# W076X.net
KiCad netlist of a schematic drawn in EAGLE
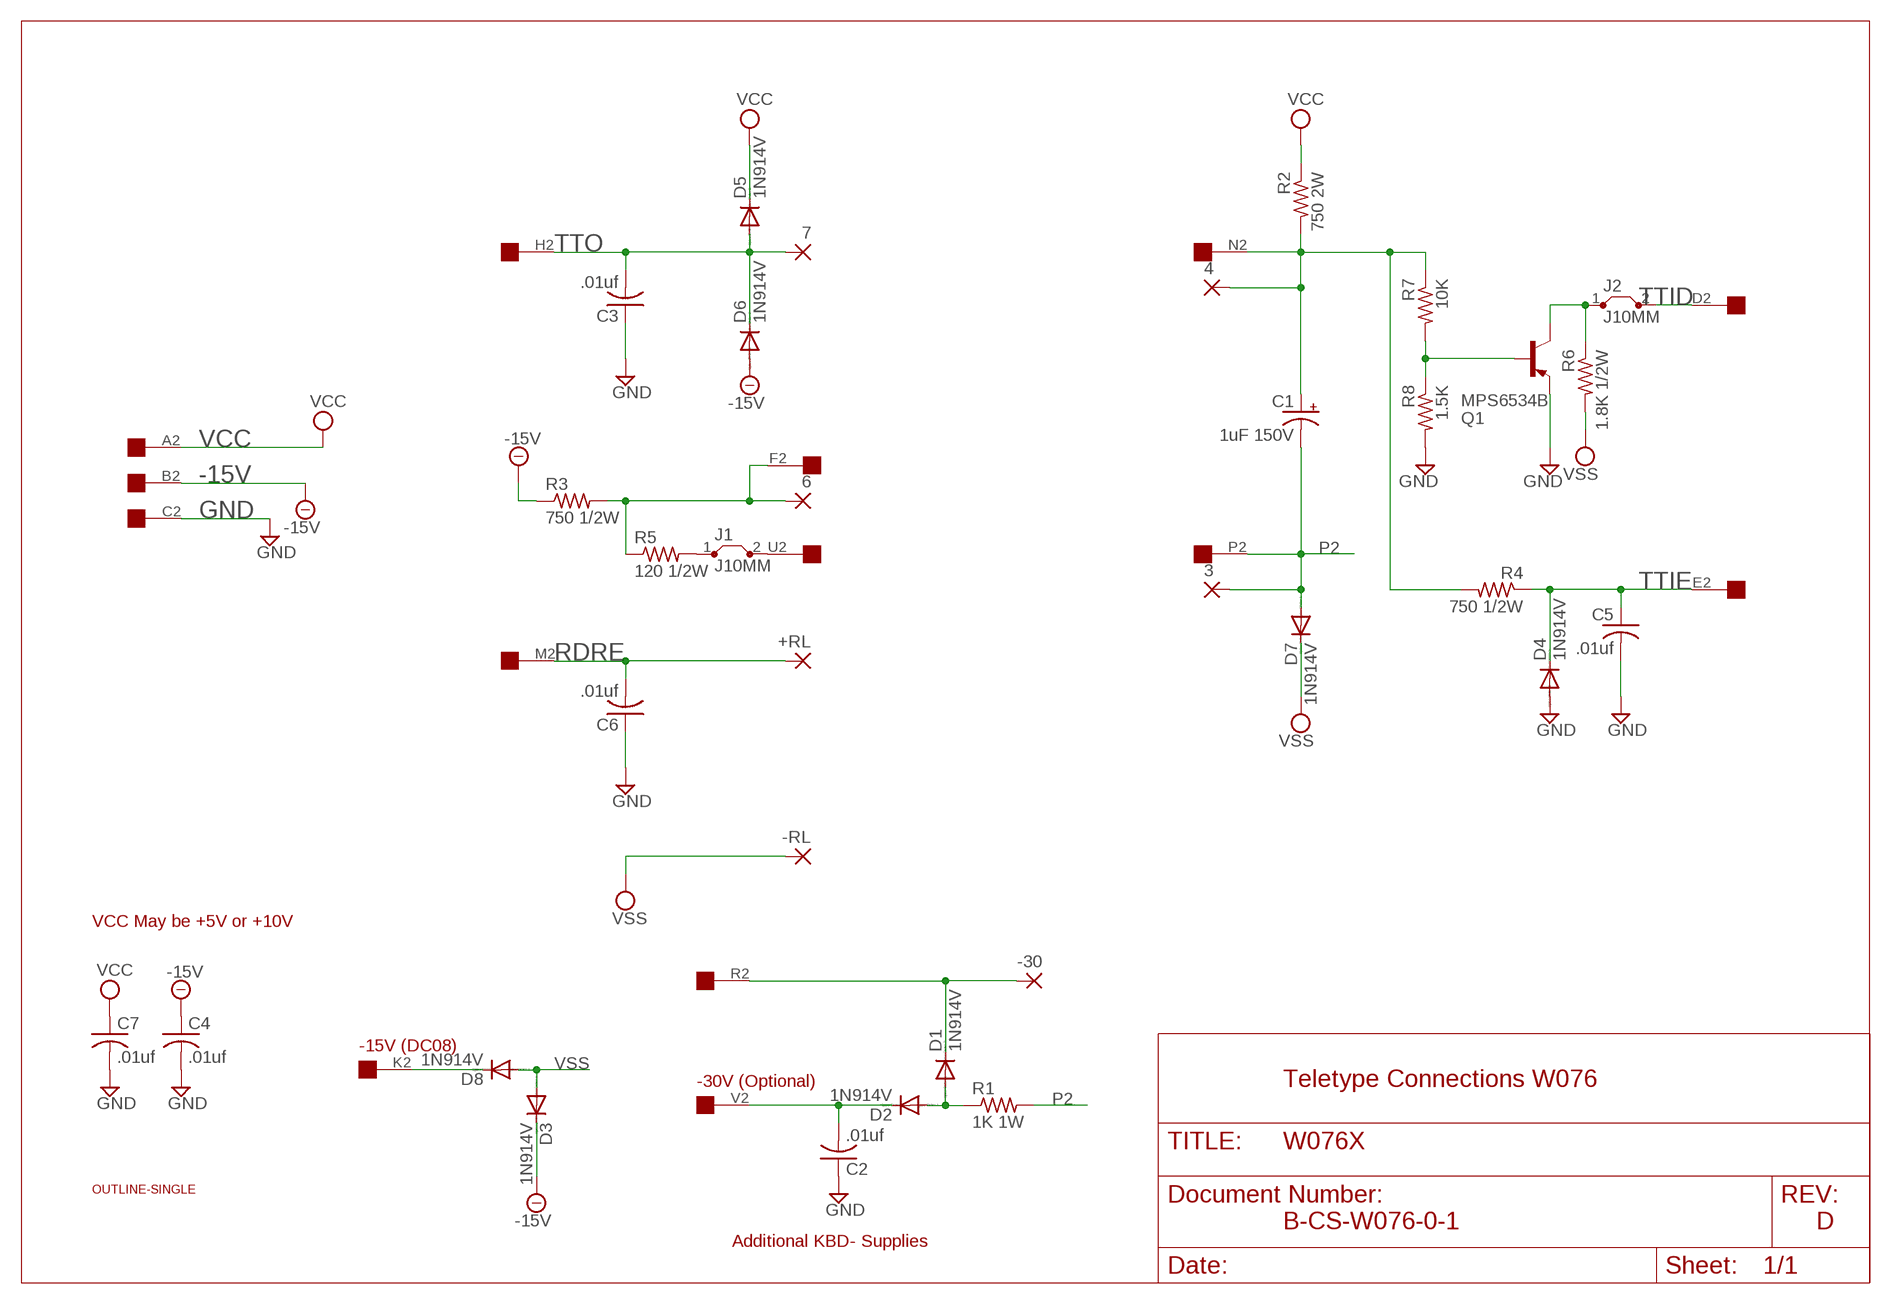
[diagram p0: schematic, sheet 1]

(export (version "E")
  (design (tool "Eeschema 10.0.6"))
  (components
    (comp (ref "+RL")
      (value "2,54/1,0")
      (footprint "eagle-import:2,54_1,0")
      (libsource (lib "eagle-import") (part "2,54/1,0"))
    )
    (comp (ref "-30")
      (value "2,54/1,0")
      (footprint "eagle-import:2,54_1,0")
      (libsource (lib "eagle-import") (part "2,54/1,0"))
    )
    (comp (ref "-RL")
      (value "2,54/1,0")
      (footprint "eagle-import:2,54_1,0")
      (libsource (lib "eagle-import") (part "2,54/1,0"))
    )
    (comp (ref "3")
      (value "2,54/1,0")
      (footprint "eagle-import:2,54_1,0")
      (libsource (lib "eagle-import") (part "2,54/1,0"))
    )
    (comp (ref "4")
      (value "2,54/1,0")
      (footprint "eagle-import:2,54_1,0")
      (libsource (lib "eagle-import") (part "2,54/1,0"))
    )
    (comp (ref "6")
      (value "2,54/1,0")
      (footprint "eagle-import:2,54_1,0")
      (libsource (lib "eagle-import") (part "2,54/1,0"))
    )
    (comp (ref "7")
      (value "2,54/1,0")
      (footprint "eagle-import:2,54_1,0")
      (libsource (lib "eagle-import") (part "2,54/1,0"))
    )
    (comp (ref "C1")
      (value "1uF 150V")
      (footprint "eagle-import:E25-9")
      (libsource (lib "eagle-import") (part "CPOL-USE25-9AXIAL"))
    )
    (comp (ref "C2")
      (value ".01uf")
      (footprint "eagle-import:C050-025X075")
      (libsource (lib "eagle-import") (part "C-US050-025X075"))
    )
    (comp (ref "C3")
      (value ".01uf")
      (footprint "eagle-import:C050-025X075")
      (libsource (lib "eagle-import") (part "C-US050-025X075"))
    )
    (comp (ref "C4")
      (value ".01uf")
      (footprint "eagle-import:C050-025X075")
      (libsource (lib "eagle-import") (part "C-US050-025X075"))
    )
    (comp (ref "C5")
      (value ".01uf")
      (footprint "eagle-import:C050-025X075")
      (libsource (lib "eagle-import") (part "C-US050-025X075"))
    )
    (comp (ref "C6")
      (value ".01uf")
      (footprint "eagle-import:C050-025X075")
      (libsource (lib "eagle-import") (part "C-US050-025X075"))
    )
    (comp (ref "C7")
      (value ".01uf")
      (footprint "eagle-import:C050-025X075")
      (libsource (lib "eagle-import") (part "C-US050-025X075"))
    )
    (comp (ref "D1")
      (value "1N914V")
      (footprint "eagle-import:DO35-10")
      (libsource (lib "eagle-import") (part "1N4148DO35-10"))
    )
    (comp (ref "D2")
      (value "1N914V")
      (footprint "eagle-import:DO35-10")
      (libsource (lib "eagle-import") (part "1N4148DO35-10"))
    )
    (comp (ref "D3")
      (value "1N914V")
      (footprint "eagle-import:DO35-10")
      (libsource (lib "eagle-import") (part "1N4148DO35-10"))
    )
    (comp (ref "D4")
      (value "1N914V")
      (footprint "eagle-import:DO35-10")
      (libsource (lib "eagle-import") (part "1N4148DO35-10"))
    )
    (comp (ref "D5")
      (value "1N914V")
      (footprint "eagle-import:DO35-10")
      (libsource (lib "eagle-import") (part "1N4148DO35-10"))
    )
    (comp (ref "D6")
      (value "1N914V")
      (footprint "eagle-import:DO35-10")
      (libsource (lib "eagle-import") (part "1N4148DO35-10"))
    )
    (comp (ref "D7")
      (value "1N914V")
      (footprint "eagle-import:DO35-10")
      (libsource (lib "eagle-import") (part "1N4148DO35-10"))
    )
    (comp (ref "D8")
      (value "1N914V")
      (footprint "eagle-import:DO35-10")
      (libsource (lib "eagle-import") (part "1N4148DO35-10"))
    )
    (comp (ref "EDGE")
      (value "EDGE-1")
      (footprint "eagle-import:EDGE-CON1")
      (libsource (lib "eagle-import") (part "EDGE-1"))
    )
    (comp (ref "J1")
      (value "J10MM")
      (footprint "eagle-import:10")
      (libsource (lib "eagle-import") (part "J10MM"))
    )
    (comp (ref "J2")
      (value "J10MM")
      (footprint "eagle-import:10")
      (libsource (lib "eagle-import") (part "J10MM"))
    )
    (comp (ref "Q1")
      (value "MPS6534B")
      (footprint "eagle-import:TO39")
      (libsource (lib "eagle-import") (part "2N2904"))
    )
    (comp (ref "R1")
      (value "1K 1W")
      (footprint "eagle-import:P0817_22")
      (libsource (lib "eagle-import") (part "R-US_0817/22"))
    )
    (comp (ref "R2")
      (value "750 2W")
      (footprint "eagle-import:P0817_22")
      (libsource (lib "eagle-import") (part "R-US_0817/22"))
    )
    (comp (ref "R3")
      (value "750 1/2W")
      (footprint "eagle-import:0411_15")
      (libsource (lib "eagle-import") (part "R-US_0411/15"))
    )
    (comp (ref "R4")
      (value "750 1/2W")
      (footprint "eagle-import:0411_15")
      (libsource (lib "eagle-import") (part "R-US_0411/15"))
    )
    (comp (ref "R5")
      (value "120 1/2W")
      (footprint "eagle-import:0411_15")
      (libsource (lib "eagle-import") (part "R-US_0411/15"))
    )
    (comp (ref "R6")
      (value "1.8K 1/2W")
      (footprint "eagle-import:0411_15")
      (libsource (lib "eagle-import") (part "R-US_0411/15"))
    )
    (comp (ref "R7")
      (value "10K")
      (footprint "eagle-import:0207_10")
      (libsource (lib "eagle-import") (part "R-US_0207/10"))
    )
    (comp (ref "R8")
      (value "1.5K")
      (footprint "eagle-import:0207_10")
      (libsource (lib "eagle-import") (part "R-US_0207/10"))
    )
    (comp (ref "U$1")
      (value "OUTLINE-SINGLE")
      (footprint "eagle-import:SINGLE")
      (libsource (lib "eagle-import") (part "OUTLINE-SINGLE"))
    )
  )
  (nets
    (net (code "1") (name "-15V") (class "Default")
      (node (ref "C4") (pin "1") (pinfunction "1_1") (pintype "passive"))
      (node (ref "D3") (pin "C") (pinfunction "C_C") (pintype "passive"))
      (node (ref "D6") (pin "A") (pinfunction "A_A") (pintype "passive"))
      (node (ref "EDGE") (pin "B2") (pinfunction "1_B2") (pintype "bidirectional"))
      (node (ref "R3") (pin "1") (pinfunction "1_1") (pintype "passive"))
    )
    (net (code "2") (name "/P2") (class "Default")
      (node (ref "3") (pin "1") (pinfunction "P_1") (pintype "passive"))
      (node (ref "C1") (pin "-") (pinfunction "-_-") (pintype "passive"))
      (node (ref "D7") (pin "A") (pinfunction "A_A") (pintype "passive"))
      (node (ref "EDGE") (pin "P2") (pinfunction "1_P2") (pintype "bidirectional"))
      (node (ref "R1") (pin "2") (pinfunction "2_2") (pintype "passive"))
    )
    (net (code "3") (name "/RDRE") (class "Default")
      (node (ref "+RL") (pin "1") (pinfunction "P_1") (pintype "passive"))
      (node (ref "C6") (pin "2") (pinfunction "2_2") (pintype "passive"))
      (node (ref "EDGE") (pin "M2") (pinfunction "1_M2") (pintype "bidirectional"))
    )
    (net (code "4") (name "/TTID") (class "Default")
      (node (ref "EDGE") (pin "D2") (pinfunction "1_D2") (pintype "bidirectional"))
      (node (ref "J2") (pin "2") (pinfunction "2_2") (pintype "passive"))
    )
    (net (code "5") (name "/TTIE") (class "Default")
      (node (ref "C5") (pin "1") (pinfunction "1_1") (pintype "passive"))
      (node (ref "D4") (pin "C") (pinfunction "C_C") (pintype "passive"))
      (node (ref "EDGE") (pin "E2") (pinfunction "1_E2") (pintype "bidirectional"))
      (node (ref "R4") (pin "1") (pinfunction "1_1") (pintype "passive"))
    )
    (net (code "6") (name "/TTO") (class "Default")
      (node (ref "7") (pin "1") (pinfunction "P_1") (pintype "passive"))
      (node (ref "C3") (pin "2") (pinfunction "2_2") (pintype "passive"))
      (node (ref "D5") (pin "A") (pinfunction "A_A") (pintype "passive"))
      (node (ref "D6") (pin "C") (pinfunction "C_C") (pintype "passive"))
      (node (ref "EDGE") (pin "H2") (pinfunction "1_H2") (pintype "bidirectional"))
    )
    (net (code "7") (name "GND") (class "Default")
      (node (ref "C2") (pin "1") (pinfunction "1_1") (pintype "passive"))
      (node (ref "C3") (pin "1") (pinfunction "1_1") (pintype "passive"))
      (node (ref "C4") (pin "2") (pinfunction "2_2") (pintype "passive"))
      (node (ref "C5") (pin "2") (pinfunction "2_2") (pintype "passive"))
      (node (ref "C6") (pin "1") (pinfunction "1_1") (pintype "passive"))
      (node (ref "C7") (pin "2") (pinfunction "2_2") (pintype "passive"))
      (node (ref "D4") (pin "A") (pinfunction "A_A") (pintype "passive"))
      (node (ref "EDGE") (pin "C2") (pinfunction "1_C2") (pintype "bidirectional"))
      (node (ref "Q1") (pin "1") (pinfunction "E_1") (pintype "passive"))
      (node (ref "R8") (pin "2") (pinfunction "2_2") (pintype "passive"))
    )
    (net (code "8") (name "Net-(-30-P)") (class "Default")
      (node (ref "-30") (pin "1") (pinfunction "P_1") (pintype "passive"))
      (node (ref "D1") (pin "C") (pinfunction "C_C") (pintype "passive"))
      (node (ref "EDGE") (pin "R2") (pinfunction "1_R2") (pintype "bidirectional"))
    )
    (net (code "9") (name "Net-(4-P)") (class "Default")
      (node (ref "4") (pin "1") (pinfunction "P_1") (pintype "passive"))
      (node (ref "C1") (pin "+") (pinfunction "+_+") (pintype "passive"))
      (node (ref "EDGE") (pin "N2") (pinfunction "1_N2") (pintype "bidirectional"))
      (node (ref "R2") (pin "2") (pinfunction "2_2") (pintype "passive"))
      (node (ref "R4") (pin "2") (pinfunction "2_2") (pintype "passive"))
      (node (ref "R7") (pin "1") (pinfunction "1_1") (pintype "passive"))
    )
    (net (code "10") (name "Net-(6-P)") (class "Default")
      (node (ref "6") (pin "1") (pinfunction "P_1") (pintype "passive"))
      (node (ref "EDGE") (pin "F2") (pinfunction "1_F2") (pintype "bidirectional"))
      (node (ref "R3") (pin "2") (pinfunction "2_2") (pintype "passive"))
      (node (ref "R5") (pin "1") (pinfunction "1_1") (pintype "passive"))
    )
    (net (code "11") (name "Net-(D1-PadA)") (class "Default")
      (node (ref "D1") (pin "A") (pinfunction "A_A") (pintype "passive"))
      (node (ref "D2") (pin "A") (pinfunction "A_A") (pintype "passive"))
      (node (ref "R1") (pin "1") (pinfunction "1_1") (pintype "passive"))
    )
    (net (code "12") (name "Net-(EDGEI-1)") (class "Default")
      (node (ref "D8") (pin "C") (pinfunction "C_C") (pintype "passive"))
      (node (ref "EDGE") (pin "K2") (pinfunction "1_K2") (pintype "bidirectional"))
    )
    (net (code "13") (name "Net-(EDGEQ-1)") (class "Default")
      (node (ref "EDGE") (pin "U2") (pinfunction "1_U2") (pintype "bidirectional"))
      (node (ref "J1") (pin "2") (pinfunction "2_2") (pintype "passive"))
    )
    (net (code "14") (name "Net-(EDGER-1)") (class "Default")
      (node (ref "C2") (pin "2") (pinfunction "2_2") (pintype "passive"))
      (node (ref "D2") (pin "C") (pinfunction "C_C") (pintype "passive"))
      (node (ref "EDGE") (pin "V2") (pinfunction "1_V2") (pintype "bidirectional"))
    )
    (net (code "15") (name "Net-(J1-Pad1)") (class "Default")
      (node (ref "J1") (pin "1") (pinfunction "1_1") (pintype "passive"))
      (node (ref "R5") (pin "2") (pinfunction "2_2") (pintype "passive"))
    )
    (net (code "16") (name "Net-(Q1-B)") (class "Default")
      (node (ref "Q1") (pin "2") (pinfunction "B_2") (pintype "passive"))
      (node (ref "R7") (pin "2") (pinfunction "2_2") (pintype "passive"))
      (node (ref "R8") (pin "1") (pinfunction "1_1") (pintype "passive"))
    )
    (net (code "17") (name "Net-(Q1-C)") (class "Default")
      (node (ref "J2") (pin "1") (pinfunction "1_1") (pintype "passive"))
      (node (ref "Q1") (pin "3") (pinfunction "C_3") (pintype "passive"))
      (node (ref "R6") (pin "1") (pinfunction "1_1") (pintype "passive"))
    )
    (net (code "18") (name "VCC") (class "Default")
      (node (ref "C7") (pin "1") (pinfunction "1_1") (pintype "passive"))
      (node (ref "D5") (pin "C") (pinfunction "C_C") (pintype "passive"))
      (node (ref "EDGE") (pin "A2") (pinfunction "1_A2") (pintype "bidirectional"))
      (node (ref "R2") (pin "1") (pinfunction "1_1") (pintype "passive"))
    )
    (net (code "19") (name "VSS") (class "Default")
      (node (ref "-RL") (pin "1") (pinfunction "P_1") (pintype "passive"))
      (node (ref "D3") (pin "A") (pinfunction "A_A") (pintype "passive"))
      (node (ref "D7") (pin "C") (pinfunction "C_C") (pintype "passive"))
      (node (ref "D8") (pin "A") (pinfunction "A_A") (pintype "passive"))
      (node (ref "R6") (pin "2") (pinfunction "2_2") (pintype "passive"))
    )
  )
)
